# Test_Jig_BMPx2.net
KiCad netlist of a schematic drawn in Altium Designer
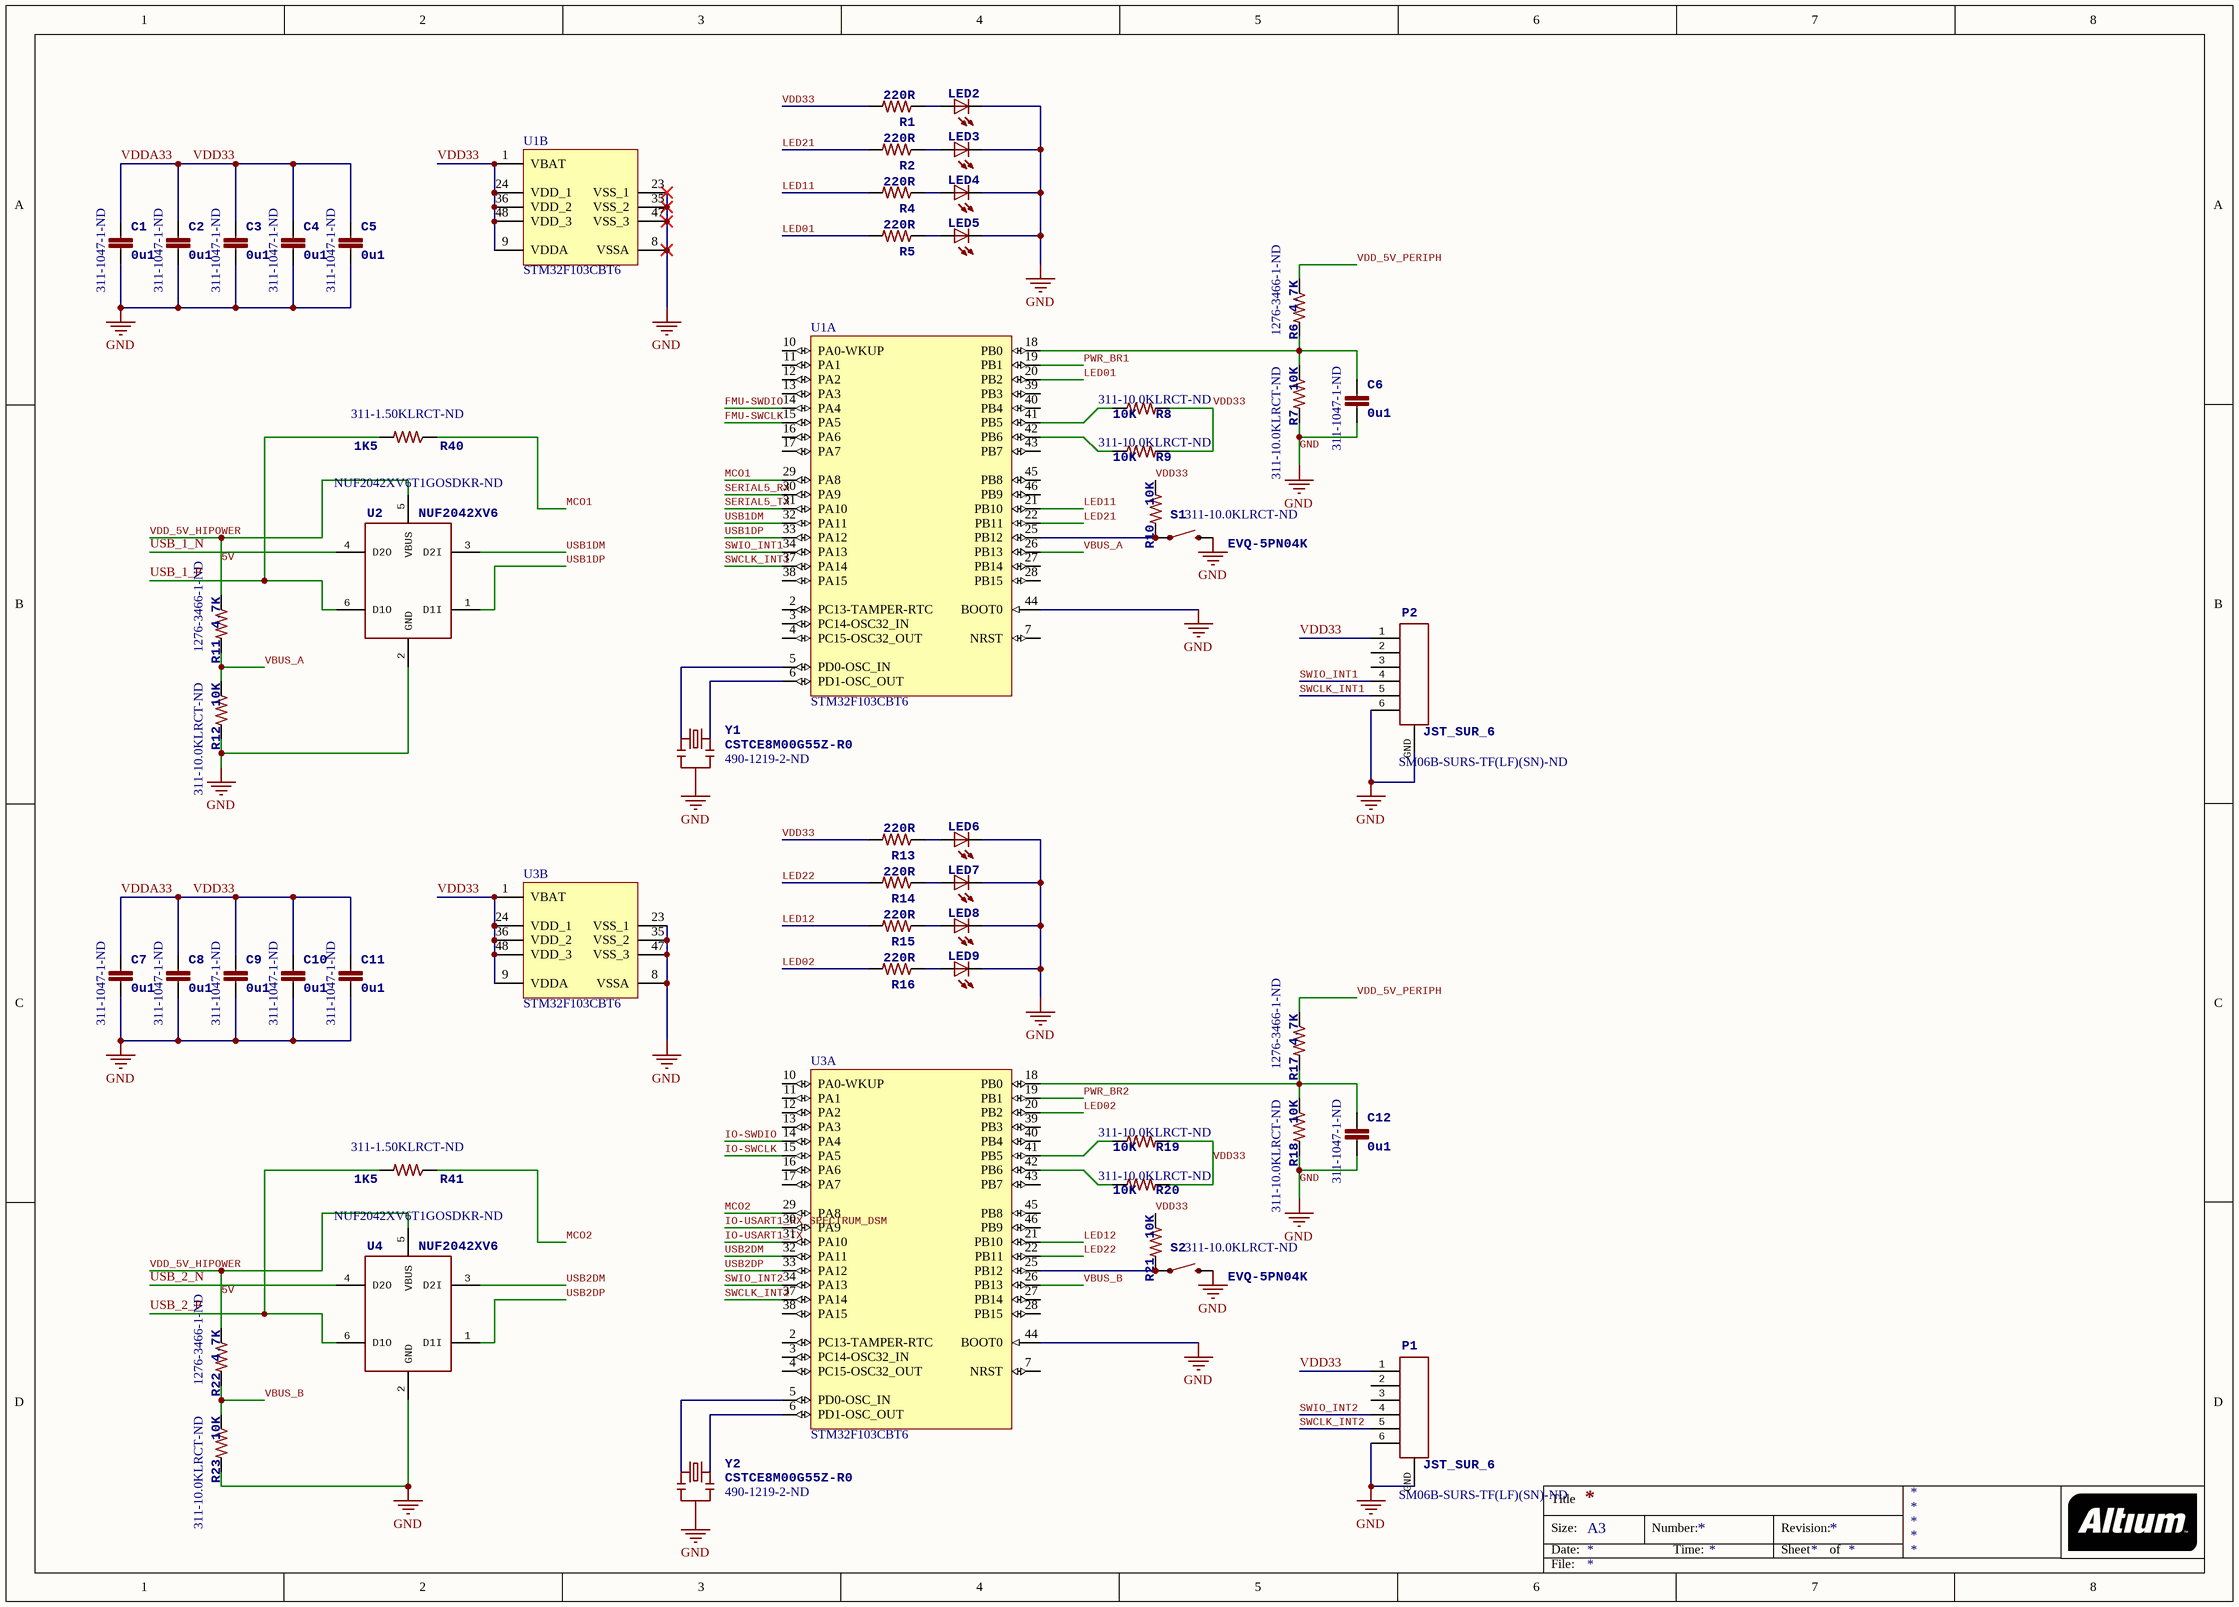
[diagram p0: Test_Jig_BMPx2.SchDoc]

(export (version "E")
  (design (tool "Eeschema 10.0.6"))
  (components
    (comp (ref "C1")
      (value "0u1")
      (footprint "0402-CAP")
      (description "CAP CER 0.1UF 16V Y5V 0402")
      (fields
        (field (name "PARTNO") "CC0402ZRY5V7BB104")
        (field (name "SUPPLIER PART NUMBER 1") "311-1047-1-ND")
        (field (name "3DR_PARTNO") "ECM0700")
      )
      (libsource (lib "pixhawk2") (part "CAP0402"))
    )
    (comp (ref "C2")
      (value "0u1")
      (footprint "0402-CAP")
      (description "CAP CER 0.1UF 16V Y5V 0402")
      (fields
        (field (name "PARTNO") "CC0402ZRY5V7BB104")
        (field (name "SUPPLIER PART NUMBER 1") "311-1047-1-ND")
        (field (name "3DR_PARTNO") "ECM0700")
      )
      (libsource (lib "pixhawk2") (part "CAP0402"))
    )
    (comp (ref "C3")
      (value "0u1")
      (footprint "0402-CAP")
      (description "CAP CER 0.1UF 16V Y5V 0402")
      (fields
        (field (name "PARTNO") "CC0402ZRY5V7BB104")
        (field (name "SUPPLIER PART NUMBER 1") "311-1047-1-ND")
        (field (name "3DR_PARTNO") "ECM0700")
      )
      (libsource (lib "pixhawk2") (part "CAP0402"))
    )
    (comp (ref "C4")
      (value "0u1")
      (footprint "0402-CAP")
      (description "CAP CER 0.1UF 16V Y5V 0402")
      (fields
        (field (name "PARTNO") "CC0402ZRY5V7BB104")
        (field (name "SUPPLIER PART NUMBER 1") "311-1047-1-ND")
        (field (name "3DR_PARTNO") "ECM0700")
      )
      (libsource (lib "pixhawk2") (part "CAP0402"))
    )
    (comp (ref "C5")
      (value "0u1")
      (footprint "0402-CAP")
      (description "CAP CER 0.1UF 16V Y5V 0402")
      (fields
        (field (name "PARTNO") "CC0402ZRY5V7BB104")
        (field (name "SUPPLIER PART NUMBER 1") "311-1047-1-ND")
        (field (name "3DR_PARTNO") "ECM0700")
      )
      (libsource (lib "pixhawk2") (part "CAP0402"))
    )
    (comp (ref "C6")
      (value "0u1")
      (footprint "0402-CAP")
      (description "CAP CER 0.1UF 16V Y5V 0402")
      (fields
        (field (name "PARTNO") "CC0402ZRY5V7BB104")
        (field (name "SUPPLIER PART NUMBER 1") "311-1047-1-ND")
        (field (name "3DR_PARTNO") "ECM0700")
      )
      (libsource (lib "pixhawk2") (part "CAP0402"))
    )
    (comp (ref "C7")
      (value "0u1")
      (footprint "0402-CAP")
      (description "CAP CER 0.1UF 16V Y5V 0402")
      (fields
        (field (name "PARTNO") "CC0402ZRY5V7BB104")
        (field (name "SUPPLIER PART NUMBER 1") "311-1047-1-ND")
        (field (name "3DR_PARTNO") "ECM0700")
      )
      (libsource (lib "pixhawk2") (part "CAP0402"))
    )
    (comp (ref "C8")
      (value "0u1")
      (footprint "0402-CAP")
      (description "CAP CER 0.1UF 16V Y5V 0402")
      (fields
        (field (name "PARTNO") "CC0402ZRY5V7BB104")
        (field (name "SUPPLIER PART NUMBER 1") "311-1047-1-ND")
        (field (name "3DR_PARTNO") "ECM0700")
      )
      (libsource (lib "pixhawk2") (part "CAP0402"))
    )
    (comp (ref "C9")
      (value "0u1")
      (footprint "0402-CAP")
      (description "CAP CER 0.1UF 16V Y5V 0402")
      (fields
        (field (name "PARTNO") "CC0402ZRY5V7BB104")
        (field (name "SUPPLIER PART NUMBER 1") "311-1047-1-ND")
        (field (name "3DR_PARTNO") "ECM0700")
      )
      (libsource (lib "pixhawk2") (part "CAP0402"))
    )
    (comp (ref "C10")
      (value "0u1")
      (footprint "0402-CAP")
      (description "CAP CER 0.1UF 16V Y5V 0402")
      (fields
        (field (name "PARTNO") "CC0402ZRY5V7BB104")
        (field (name "SUPPLIER PART NUMBER 1") "311-1047-1-ND")
        (field (name "3DR_PARTNO") "ECM0700")
      )
      (libsource (lib "pixhawk2") (part "CAP0402"))
    )
    (comp (ref "C11")
      (value "0u1")
      (footprint "0402-CAP")
      (description "CAP CER 0.1UF 16V Y5V 0402")
      (fields
        (field (name "PARTNO") "CC0402ZRY5V7BB104")
        (field (name "SUPPLIER PART NUMBER 1") "311-1047-1-ND")
        (field (name "3DR_PARTNO") "ECM0700")
      )
      (libsource (lib "pixhawk2") (part "CAP0402"))
    )
    (comp (ref "C12")
      (value "0u1")
      (footprint "0402-CAP")
      (description "CAP CER 0.1UF 16V Y5V 0402")
      (fields
        (field (name "PARTNO") "CC0402ZRY5V7BB104")
        (field (name "SUPPLIER PART NUMBER 1") "311-1047-1-ND")
        (field (name "3DR_PARTNO") "ECM0700")
      )
      (libsource (lib "pixhawk2") (part "CAP0402"))
    )
    (comp (ref "LED2")
      (value "LED0603_Green")
      (footprint "0603-LED-Blue")
      (description "LED GREEN ROUND CLEAR SMD")
      (fields (field (name "3DR_PARTNO") "ECM0494") (field (name "PARTNO") "APTD1608CGCK"))
      (libsource (lib "pixhawk2") (part "LED0603_Blue"))
    )
    (comp (ref "LED3")
      (value "LED0603_Green")
      (footprint "0603-LED-Blue")
      (description "LED GREEN ROUND CLEAR SMD")
      (fields (field (name "3DR_PARTNO") "ECM0494") (field (name "PARTNO") "APTD1608CGCK"))
      (libsource (lib "pixhawk2") (part "LED0603_Blue"))
    )
    (comp (ref "LED4")
      (value "LED0603_Green")
      (footprint "0603-LED-Blue")
      (description "LED GREEN ROUND CLEAR SMD")
      (fields (field (name "3DR_PARTNO") "ECM0494") (field (name "PARTNO") "APTD1608CGCK"))
      (libsource (lib "pixhawk2") (part "LED0603_Blue"))
    )
    (comp (ref "LED5")
      (value "LED0603_Green")
      (footprint "0603-LED-Blue")
      (description "LED GREEN ROUND CLEAR SMD")
      (fields (field (name "3DR_PARTNO") "ECM0494") (field (name "PARTNO") "APTD1608CGCK"))
      (libsource (lib "pixhawk2") (part "LED0603_Blue"))
    )
    (comp (ref "LED6")
      (value "LED0603_Green")
      (footprint "0603-LED-Blue")
      (description "LED GREEN ROUND CLEAR SMD")
      (fields (field (name "3DR_PARTNO") "ECM0494") (field (name "PARTNO") "APTD1608CGCK"))
      (libsource (lib "pixhawk2") (part "LED0603_Blue"))
    )
    (comp (ref "LED7")
      (value "LED0603_Green")
      (footprint "0603-LED-Blue")
      (description "LED GREEN ROUND CLEAR SMD")
      (fields (field (name "3DR_PARTNO") "ECM0494") (field (name "PARTNO") "APTD1608CGCK"))
      (libsource (lib "pixhawk2") (part "LED0603_Blue"))
    )
    (comp (ref "LED8")
      (value "LED0603_Green")
      (footprint "0603-LED-Blue")
      (description "LED GREEN ROUND CLEAR SMD")
      (fields (field (name "3DR_PARTNO") "ECM0494") (field (name "PARTNO") "APTD1608CGCK"))
      (libsource (lib "pixhawk2") (part "LED0603_Blue"))
    )
    (comp (ref "LED9")
      (value "LED0603_Green")
      (footprint "0603-LED-Blue")
      (description "LED GREEN ROUND CLEAR SMD")
      (fields (field (name "3DR_PARTNO") "ECM0494") (field (name "PARTNO") "APTD1608CGCK"))
      (libsource (lib "pixhawk2") (part "LED0603_Blue"))
    )
    (comp (ref "P1")
      (value "JST_SUR_6")
      (footprint "JST_SUR_H6")
      (description "Connector, Header, 6Pos, .8mm IDC, R/A, SMD, Tin")
      (fields
        (field (name "SUPPLIER PART NUMBER 1") "SM06B-SURS-TF(LF)(SN)-ND")
        (field (name "3DR_PARTNO") "PRT0442")
      )
      (libsource (lib "PCA_0005_FULL_CB_REV_A") (part "JST_SUR_6"))
    )
    (comp (ref "P2")
      (value "JST_SUR_6")
      (footprint "JST_SUR_H6")
      (description "Connector, Header, 6Pos, .8mm IDC, R/A, SMD, Tin")
      (fields
        (field (name "SUPPLIER PART NUMBER 1") "SM06B-SURS-TF(LF)(SN)-ND")
        (field (name "3DR_PARTNO") "PRT0442")
      )
      (libsource (lib "PCA_0005_FULL_CB_REV_A") (part "JST_SUR_6"))
    )
    (comp (ref "R1")
      (value "220R")
      (footprint "0402-RES")
      (description "RES 220 OHM 1/16W 1% 0402 SMD")
      (fields (field (name "PARTNO") "RC0402FR-07220RL") (field (name "3DR_PARTNO") "ECM0821"))
      (libsource (lib "pixhawk2") (part "RESISTOR0402-RES"))
    )
    (comp (ref "R2")
      (value "220R")
      (footprint "0402-RES")
      (description "RES 220 OHM 1/16W 1% 0402 SMD")
      (fields (field (name "PARTNO") "RC0402FR-07220RL") (field (name "3DR_PARTNO") "ECM0821"))
      (libsource (lib "pixhawk2") (part "RESISTOR0402-RES"))
    )
    (comp (ref "R4")
      (value "220R")
      (footprint "0402-RES")
      (description "RES 220 OHM 1/16W 1% 0402 SMD")
      (fields (field (name "PARTNO") "RC0402FR-07220RL") (field (name "3DR_PARTNO") "ECM0821"))
      (libsource (lib "pixhawk2") (part "RESISTOR0402-RES"))
    )
    (comp (ref "R5")
      (value "220R")
      (footprint "0402-RES")
      (description "RES 220 OHM 1/16W 1% 0402 SMD")
      (fields (field (name "PARTNO") "RC0402FR-07220RL") (field (name "3DR_PARTNO") "ECM0821"))
      (libsource (lib "pixhawk2") (part "RESISTOR0402-RES"))
    )
    (comp (ref "R6")
      (value "4.7K")
      (footprint "0402-RES")
      (description "RES 10K OHM 1/16W 1% 0402 SMD")
      (fields (field (name "PARTNO") "RC1005F472CS") (field (name "SUPPLIER PART NUMBER 1") "1276-3466-1-ND"))
      (libsource (lib "pixhawk2") (part "RESISTOR0402-RES"))
    )
    (comp (ref "R7")
      (value "10K")
      (footprint "0402-RES")
      (description "RES 10K OHM 1/16W 1% 0402 SMD")
      (fields
        (field (name "PARTNO") "RC0402FR-0710KL")
        (field (name "SUPPLIER PART NUMBER 1") "311-10.0KLRCT-ND")
        (field (name "3DR_PARTNO") "ECM0800")
      )
      (libsource (lib "pixhawk2") (part "RESISTOR0402-RES"))
    )
    (comp (ref "R8")
      (value "10K")
      (footprint "0402-RES")
      (description "RES 10K OHM 1/16W 1% 0402 SMD")
      (fields
        (field (name "PARTNO") "RC0402FR-0710KL")
        (field (name "SUPPLIER PART NUMBER 1") "311-10.0KLRCT-ND")
        (field (name "3DR_PARTNO") "ECM0800")
      )
      (libsource (lib "pixhawk2") (part "RESISTOR0402-RES"))
    )
    (comp (ref "R9")
      (value "10K")
      (footprint "0402-RES")
      (description "RES 10K OHM 1/16W 1% 0402 SMD")
      (fields
        (field (name "PARTNO") "RC0402FR-0710KL")
        (field (name "SUPPLIER PART NUMBER 1") "311-10.0KLRCT-ND")
        (field (name "3DR_PARTNO") "ECM0800")
      )
      (libsource (lib "pixhawk2") (part "RESISTOR0402-RES"))
    )
    (comp (ref "R10")
      (value "10K")
      (footprint "0402-RES")
      (description "RES 10K OHM 1/16W 1% 0402 SMD")
      (fields
        (field (name "PARTNO") "RC0402FR-0710KL")
        (field (name "SUPPLIER PART NUMBER 1") "311-10.0KLRCT-ND")
        (field (name "3DR_PARTNO") "ECM0800")
      )
      (libsource (lib "pixhawk2") (part "RESISTOR0402-RES"))
    )
    (comp (ref "R11")
      (value "4.7K")
      (footprint "0402-RES")
      (description "RES 10K OHM 1/16W 1% 0402 SMD")
      (fields (field (name "PARTNO") "RC1005F472CS") (field (name "SUPPLIER PART NUMBER 1") "1276-3466-1-ND"))
      (libsource (lib "pixhawk2") (part "RESISTOR0402-RES"))
    )
    (comp (ref "R12")
      (value "10K")
      (footprint "0402-RES")
      (description "RES 10K OHM 1/16W 1% 0402 SMD")
      (fields
        (field (name "PARTNO") "RC0402FR-0710KL")
        (field (name "SUPPLIER PART NUMBER 1") "311-10.0KLRCT-ND")
        (field (name "3DR_PARTNO") "ECM0800")
      )
      (libsource (lib "pixhawk2") (part "RESISTOR0402-RES"))
    )
    (comp (ref "R13")
      (value "220R")
      (footprint "0402-RES")
      (description "RES 220 OHM 1/16W 1% 0402 SMD")
      (fields (field (name "PARTNO") "RC0402FR-07220RL") (field (name "3DR_PARTNO") "ECM0821"))
      (libsource (lib "pixhawk2") (part "RESISTOR0402-RES"))
    )
    (comp (ref "R14")
      (value "220R")
      (footprint "0402-RES")
      (description "RES 220 OHM 1/16W 1% 0402 SMD")
      (fields (field (name "PARTNO") "RC0402FR-07220RL") (field (name "3DR_PARTNO") "ECM0821"))
      (libsource (lib "pixhawk2") (part "RESISTOR0402-RES"))
    )
    (comp (ref "R15")
      (value "220R")
      (footprint "0402-RES")
      (description "RES 220 OHM 1/16W 1% 0402 SMD")
      (fields (field (name "PARTNO") "RC0402FR-07220RL") (field (name "3DR_PARTNO") "ECM0821"))
      (libsource (lib "pixhawk2") (part "RESISTOR0402-RES"))
    )
    (comp (ref "R16")
      (value "220R")
      (footprint "0402-RES")
      (description "RES 220 OHM 1/16W 1% 0402 SMD")
      (fields (field (name "PARTNO") "RC0402FR-07220RL") (field (name "3DR_PARTNO") "ECM0821"))
      (libsource (lib "pixhawk2") (part "RESISTOR0402-RES"))
    )
    (comp (ref "R17")
      (value "4.7K")
      (footprint "0402-RES")
      (description "RES 10K OHM 1/16W 1% 0402 SMD")
      (fields (field (name "PARTNO") "RC1005F472CS") (field (name "SUPPLIER PART NUMBER 1") "1276-3466-1-ND"))
      (libsource (lib "pixhawk2") (part "RESISTOR0402-RES"))
    )
    (comp (ref "R18")
      (value "10K")
      (footprint "0402-RES")
      (description "RES 10K OHM 1/16W 1% 0402 SMD")
      (fields
        (field (name "PARTNO") "RC0402FR-0710KL")
        (field (name "SUPPLIER PART NUMBER 1") "311-10.0KLRCT-ND")
        (field (name "3DR_PARTNO") "ECM0800")
      )
      (libsource (lib "pixhawk2") (part "RESISTOR0402-RES"))
    )
    (comp (ref "R19")
      (value "10K")
      (footprint "0402-RES")
      (description "RES 10K OHM 1/16W 1% 0402 SMD")
      (fields
        (field (name "PARTNO") "RC0402FR-0710KL")
        (field (name "SUPPLIER PART NUMBER 1") "311-10.0KLRCT-ND")
        (field (name "3DR_PARTNO") "ECM0800")
      )
      (libsource (lib "pixhawk2") (part "RESISTOR0402-RES"))
    )
    (comp (ref "R20")
      (value "10K")
      (footprint "0402-RES")
      (description "RES 10K OHM 1/16W 1% 0402 SMD")
      (fields
        (field (name "PARTNO") "RC0402FR-0710KL")
        (field (name "SUPPLIER PART NUMBER 1") "311-10.0KLRCT-ND")
        (field (name "3DR_PARTNO") "ECM0800")
      )
      (libsource (lib "pixhawk2") (part "RESISTOR0402-RES"))
    )
    (comp (ref "R21")
      (value "10K")
      (footprint "0402-RES")
      (description "RES 10K OHM 1/16W 1% 0402 SMD")
      (fields
        (field (name "PARTNO") "RC0402FR-0710KL")
        (field (name "SUPPLIER PART NUMBER 1") "311-10.0KLRCT-ND")
        (field (name "3DR_PARTNO") "ECM0800")
      )
      (libsource (lib "pixhawk2") (part "RESISTOR0402-RES"))
    )
    (comp (ref "R22")
      (value "4.7K")
      (footprint "0402-RES")
      (description "RES 10K OHM 1/16W 1% 0402 SMD")
      (fields (field (name "PARTNO") "RC1005F472CS") (field (name "SUPPLIER PART NUMBER 1") "1276-3466-1-ND"))
      (libsource (lib "pixhawk2") (part "RESISTOR0402-RES"))
    )
    (comp (ref "R23")
      (value "10K")
      (footprint "0402-RES")
      (description "RES 10K OHM 1/16W 1% 0402 SMD")
      (fields
        (field (name "PARTNO") "RC0402FR-0710KL")
        (field (name "SUPPLIER PART NUMBER 1") "311-10.0KLRCT-ND")
        (field (name "3DR_PARTNO") "ECM0800")
      )
      (libsource (lib "pixhawk2") (part "RESISTOR0402-RES"))
    )
    (comp (ref "R40")
      (value "1K5")
      (footprint "0402-RES")
      (description "RES 1.5K OHM 1/16W 1% 0402 SMD")
      (fields
        (field (name "PARTNO") "RC0402FR-071K5L")
        (field (name "SUPPLIER PART NUMBER 1") "311-1.50KLRCT-ND")
        (field (name "3DR_PARTNO") "ECM0803")
      )
      (libsource (lib "pixhawk2") (part "RESISTOR0402-RES"))
    )
    (comp (ref "R41")
      (value "1K5")
      (footprint "0402-RES")
      (description "RES 1.5K OHM 1/16W 1% 0402 SMD")
      (fields
        (field (name "PARTNO") "RC0402FR-071K5L")
        (field (name "SUPPLIER PART NUMBER 1") "311-1.50KLRCT-ND")
        (field (name "3DR_PARTNO") "ECM0803")
      )
      (libsource (lib "pixhawk2") (part "RESISTOR0402-RES"))
    )
    (comp (ref "S1")
      (value "EVQ-5PN04K")
      (footprint "TACTILE-SWITCH-1101NE")
      (libsource (lib "pixhawk2") (part "SWITCH-MOMENTARY-2-SMD-1101NE"))
    )
    (comp (ref "S2")
      (value "EVQ-5PN04K")
      (footprint "TACTILE-SWITCH-1101NE")
      (libsource (lib "pixhawk2") (part "SWITCH-MOMENTARY-2-SMD-1101NE"))
    )
    (comp (ref "U1")
      (value "STM32F103CBT6")
      (footprint "STM-LQFP48_N")
      (libsource (lib "STMicroelectronics STM32 F1") (part "STM32F103CBT6"))
    )
    (comp (ref "U2")
      (value "NUF2042XV6")
      (footprint "SOT563-6")
      (description "IC FILTER USB ESD PROTECT SOT363")
      (fields
        (field (name "PARTNO") "NUF2042XV6T1G")
        (field (name "SUPPLIER PART NUMBER 1") "NUF2042XV6T1GOSDKR-ND")
        (field (name "3DR_PARTNO") "ECM0836")
      )
      (libsource (lib "pixhawk2") (part "NUF2042XV6"))
    )
    (comp (ref "U3")
      (value "STM32F103CBT6")
      (footprint "STM-LQFP48_N")
      (libsource (lib "STMicroelectronics STM32 F1") (part "STM32F103CBT6"))
    )
    (comp (ref "U4")
      (value "NUF2042XV6")
      (footprint "SOT563-6")
      (description "IC FILTER USB ESD PROTECT SOT363")
      (fields
        (field (name "PARTNO") "NUF2042XV6T1G")
        (field (name "SUPPLIER PART NUMBER 1") "NUF2042XV6T1GOSDKR-ND")
        (field (name "3DR_PARTNO") "ECM0836")
      )
      (libsource (lib "pixhawk2") (part "NUF2042XV6"))
    )
    (comp (ref "Y1")
      (value "CSTCE8M00G55Z-R0")
      (footprint "RESONATOR-SMD")
      (fields (field (name "SUPPLIER PART NUMBER 1") "490-1219-2-ND"))
      (libsource (lib "SparkFun") (part "RESONATORSMD"))
    )
    (comp (ref "Y2")
      (value "CSTCE8M00G55Z-R0")
      (footprint "RESONATOR-SMD")
      (fields (field (name "SUPPLIER PART NUMBER 1") "490-1219-2-ND"))
      (libsource (lib "SparkFun") (part "RESONATORSMD"))
    )
  )
  (nets
    (net (code "1") (name "/5V") (class "Default")
      (node (ref "R11") (pin "P$1") (pinfunction "1_P$1") (pintype "passive"))
      (node (ref "R22") (pin "P$1") (pinfunction "1_P$1") (pintype "passive"))
      (node (ref "U2") (pin "5") (pinfunction "VBUS_5") (pintype "passive"))
      (node (ref "U4") (pin "5") (pinfunction "VBUS_5") (pintype "passive"))
    )
    (net (code "2") (name "/FMU-SWCLK") (class "Default")
      (node (ref "U1") (pin "15") (pinfunction "PA5_15") (pintype "bidirectional"))
    )
    (net (code "3") (name "/FMU-SWDIO") (class "Default")
      (node (ref "U1") (pin "14") (pinfunction "PA4_14") (pintype "bidirectional"))
    )
    (net (code "4") (name "/IO-SWCLK") (class "Default")
      (node (ref "U3") (pin "15") (pinfunction "PA5_15") (pintype "bidirectional"))
    )
    (net (code "5") (name "/IO-SWDIO") (class "Default")
      (node (ref "U3") (pin "14") (pinfunction "PA4_14") (pintype "bidirectional"))
    )
    (net (code "6") (name "/IO-USART1_RX_SPECTRUM_DSM") (class "Default")
      (node (ref "U3") (pin "30") (pinfunction "PA9_30") (pintype "bidirectional"))
    )
    (net (code "7") (name "/IO-USART1_TX") (class "Default")
      (node (ref "U3") (pin "31") (pinfunction "PA10_31") (pintype "bidirectional"))
    )
    (net (code "8") (name "/LED01") (class "Default")
      (node (ref "R5") (pin "P$2") (pinfunction "2_P$2") (pintype "passive"))
      (node (ref "U1") (pin "20") (pinfunction "PB2_20") (pintype "bidirectional"))
    )
    (net (code "9") (name "/LED02") (class "Default")
      (node (ref "R16") (pin "P$2") (pinfunction "2_P$2") (pintype "passive"))
      (node (ref "U3") (pin "20") (pinfunction "PB2_20") (pintype "bidirectional"))
    )
    (net (code "10") (name "/LED11") (class "Default")
      (node (ref "R4") (pin "P$2") (pinfunction "2_P$2") (pintype "passive"))
      (node (ref "U1") (pin "21") (pinfunction "PB10_21") (pintype "bidirectional"))
    )
    (net (code "11") (name "/LED12") (class "Default")
      (node (ref "R15") (pin "P$2") (pinfunction "2_P$2") (pintype "passive"))
      (node (ref "U3") (pin "21") (pinfunction "PB10_21") (pintype "bidirectional"))
    )
    (net (code "12") (name "/LED21") (class "Default")
      (node (ref "R2") (pin "P$2") (pinfunction "2_P$2") (pintype "passive"))
      (node (ref "U1") (pin "22") (pinfunction "PB11_22") (pintype "bidirectional"))
    )
    (net (code "13") (name "/LED22") (class "Default")
      (node (ref "R14") (pin "P$2") (pinfunction "2_P$2") (pintype "passive"))
      (node (ref "U3") (pin "22") (pinfunction "PB11_22") (pintype "bidirectional"))
    )
    (net (code "14") (name "/MCO1") (class "Default")
      (node (ref "R40") (pin "P$1") (pinfunction "1_P$1") (pintype "passive"))
      (node (ref "U1") (pin "29") (pinfunction "PA8_29") (pintype "bidirectional"))
    )
    (net (code "15") (name "/MCO2") (class "Default")
      (node (ref "R41") (pin "P$1") (pinfunction "1_P$1") (pintype "passive"))
      (node (ref "U3") (pin "29") (pinfunction "PA8_29") (pintype "bidirectional"))
    )
    (net (code "16") (name "/PWR_BR1") (class "Default")
      (node (ref "U1") (pin "19") (pinfunction "PB1_19") (pintype "bidirectional"))
    )
    (net (code "17") (name "/PWR_BR2") (class "Default")
      (node (ref "U3") (pin "19") (pinfunction "PB1_19") (pintype "bidirectional"))
    )
    (net (code "18") (name "/SERIAL5_RX") (class "Default")
      (node (ref "U1") (pin "30") (pinfunction "PA9_30") (pintype "bidirectional"))
    )
    (net (code "19") (name "/SERIAL5_TX") (class "Default")
      (node (ref "U1") (pin "31") (pinfunction "PA10_31") (pintype "bidirectional"))
    )
    (net (code "20") (name "/SWCLK_INT1") (class "Default")
      (node (ref "P2") (pin "5") (pinfunction "5_5") (pintype "passive"))
      (node (ref "U1") (pin "37") (pinfunction "PA14_37") (pintype "bidirectional"))
    )
    (net (code "21") (name "/SWCLK_INT2") (class "Default")
      (node (ref "P1") (pin "5") (pinfunction "5_5") (pintype "passive"))
      (node (ref "U3") (pin "37") (pinfunction "PA14_37") (pintype "bidirectional"))
    )
    (net (code "22") (name "/SWIO_INT1") (class "Default")
      (node (ref "P2") (pin "4") (pinfunction "4_4") (pintype "passive"))
      (node (ref "U1") (pin "34") (pinfunction "PA13_34") (pintype "bidirectional"))
    )
    (net (code "23") (name "/SWIO_INT2") (class "Default")
      (node (ref "P1") (pin "4") (pinfunction "4_4") (pintype "passive"))
      (node (ref "U3") (pin "34") (pinfunction "PA13_34") (pintype "bidirectional"))
    )
    (net (code "24") (name "/USB1DM") (class "Default")
      (node (ref "U1") (pin "32") (pinfunction "PA11_32") (pintype "bidirectional"))
      (node (ref "U2") (pin "3") (pinfunction "D2I_3") (pintype "passive"))
    )
    (net (code "25") (name "/USB1DP") (class "Default")
      (node (ref "U1") (pin "33") (pinfunction "PA12_33") (pintype "bidirectional"))
      (node (ref "U2") (pin "1") (pinfunction "D1I_1") (pintype "passive"))
    )
    (net (code "26") (name "/USB2DM") (class "Default")
      (node (ref "U3") (pin "32") (pinfunction "PA11_32") (pintype "bidirectional"))
      (node (ref "U4") (pin "3") (pinfunction "D2I_3") (pintype "passive"))
    )
    (net (code "27") (name "/USB2DP") (class "Default")
      (node (ref "U3") (pin "33") (pinfunction "PA12_33") (pintype "bidirectional"))
      (node (ref "U4") (pin "1") (pinfunction "D1I_1") (pintype "passive"))
    )
    (net (code "28") (name "/USB_1_N") (class "Default")
      (node (ref "U2") (pin "4") (pinfunction "D2O_4") (pintype "passive"))
    )
    (net (code "29") (name "/USB_1_P") (class "Default")
      (node (ref "R40") (pin "P$2") (pinfunction "2_P$2") (pintype "passive"))
      (node (ref "U2") (pin "6") (pinfunction "D1O_6") (pintype "passive"))
    )
    (net (code "30") (name "/USB_2_N") (class "Default")
      (node (ref "U4") (pin "4") (pinfunction "D2O_4") (pintype "passive"))
    )
    (net (code "31") (name "/USB_2_P") (class "Default")
      (node (ref "R41") (pin "P$2") (pinfunction "2_P$2") (pintype "passive"))
      (node (ref "U4") (pin "6") (pinfunction "D1O_6") (pintype "passive"))
    )
    (net (code "32") (name "/VBUS_A") (class "Default")
      (node (ref "R11") (pin "P$2") (pinfunction "2_P$2") (pintype "passive"))
      (node (ref "R12") (pin "P$1") (pinfunction "1_P$1") (pintype "passive"))
      (node (ref "U1") (pin "26") (pinfunction "PB13_26") (pintype "bidirectional"))
    )
    (net (code "33") (name "/VBUS_B") (class "Default")
      (node (ref "R22") (pin "P$2") (pinfunction "2_P$2") (pintype "passive"))
      (node (ref "R23") (pin "P$1") (pinfunction "1_P$1") (pintype "passive"))
      (node (ref "U3") (pin "26") (pinfunction "PB13_26") (pintype "bidirectional"))
    )
    (net (code "34") (name "/VDD33") (class "Default")
      (node (ref "C1") (pin "P$1") (pinfunction "1_P$1") (pintype "passive"))
      (node (ref "C10") (pin "P$1") (pinfunction "1_P$1") (pintype "passive"))
      (node (ref "C11") (pin "P$1") (pinfunction "1_P$1") (pintype "passive"))
      (node (ref "C2") (pin "P$1") (pinfunction "1_P$1") (pintype "passive"))
      (node (ref "C3") (pin "P$1") (pinfunction "1_P$1") (pintype "passive"))
      (node (ref "C4") (pin "P$1") (pinfunction "1_P$1") (pintype "passive"))
      (node (ref "C5") (pin "P$1") (pinfunction "1_P$1") (pintype "passive"))
      (node (ref "C7") (pin "P$1") (pinfunction "1_P$1") (pintype "passive"))
      (node (ref "C8") (pin "P$1") (pinfunction "1_P$1") (pintype "passive"))
      (node (ref "C9") (pin "P$1") (pinfunction "1_P$1") (pintype "passive"))
      (node (ref "P1") (pin "1") (pinfunction "1_1") (pintype "passive"))
      (node (ref "P2") (pin "1") (pinfunction "1_1") (pintype "passive"))
      (node (ref "R1") (pin "P$2") (pinfunction "2_P$2") (pintype "passive"))
      (node (ref "R10") (pin "P$1") (pinfunction "1_P$1") (pintype "passive"))
      (node (ref "R13") (pin "P$2") (pinfunction "2_P$2") (pintype "passive"))
      (node (ref "R19") (pin "P$2") (pinfunction "2_P$2") (pintype "passive"))
      (node (ref "R20") (pin "P$2") (pinfunction "2_P$2") (pintype "passive"))
      (node (ref "R21") (pin "P$1") (pinfunction "1_P$1") (pintype "passive"))
      (node (ref "R8") (pin "P$2") (pinfunction "2_P$2") (pintype "passive"))
      (node (ref "R9") (pin "P$2") (pinfunction "2_P$2") (pintype "passive"))
      (node (ref "U1") (pin "1") (pinfunction "VBAT_1") (pintype "power_in"))
      (node (ref "U1") (pin "24") (pinfunction "VDD_1_24") (pintype "power_in"))
      (node (ref "U1") (pin "36") (pinfunction "VDD_2_36") (pintype "power_in"))
      (node (ref "U1") (pin "48") (pinfunction "VDD_3_48") (pintype "power_in"))
      (node (ref "U1") (pin "9") (pinfunction "VDDA_9") (pintype "power_in"))
      (node (ref "U3") (pin "1") (pinfunction "VBAT_1") (pintype "power_in"))
      (node (ref "U3") (pin "24") (pinfunction "VDD_1_24") (pintype "power_in"))
      (node (ref "U3") (pin "36") (pinfunction "VDD_2_36") (pintype "power_in"))
      (node (ref "U3") (pin "48") (pinfunction "VDD_3_48") (pintype "power_in"))
      (node (ref "U3") (pin "9") (pinfunction "VDDA_9") (pintype "power_in"))
    )
    (net (code "35") (name "/VDD_5V_PERIPH") (class "Default")
      (node (ref "R17") (pin "P$1") (pinfunction "1_P$1") (pintype "passive"))
      (node (ref "R6") (pin "P$1") (pinfunction "1_P$1") (pintype "passive"))
    )
    (net (code "36") (name "GND") (class "Default")
      (node (ref "C1") (pin "P$2") (pinfunction "2_P$2") (pintype "passive"))
      (node (ref "C10") (pin "P$2") (pinfunction "2_P$2") (pintype "passive"))
      (node (ref "C11") (pin "P$2") (pinfunction "2_P$2") (pintype "passive"))
      (node (ref "C12") (pin "P$2") (pinfunction "2_P$2") (pintype "passive"))
      (node (ref "C2") (pin "P$2") (pinfunction "2_P$2") (pintype "passive"))
      (node (ref "C3") (pin "P$2") (pinfunction "2_P$2") (pintype "passive"))
      (node (ref "C4") (pin "P$2") (pinfunction "2_P$2") (pintype "passive"))
      (node (ref "C5") (pin "P$2") (pinfunction "2_P$2") (pintype "passive"))
      (node (ref "C6") (pin "P$2") (pinfunction "2_P$2") (pintype "passive"))
      (node (ref "C7") (pin "P$2") (pinfunction "2_P$2") (pintype "passive"))
      (node (ref "C8") (pin "P$2") (pinfunction "2_P$2") (pintype "passive"))
      (node (ref "C9") (pin "P$2") (pinfunction "2_P$2") (pintype "passive"))
      (node (ref "LED2") (pin "C") (pinfunction "C_C") (pintype "passive"))
      (node (ref "LED3") (pin "C") (pinfunction "C_C") (pintype "passive"))
      (node (ref "LED4") (pin "C") (pinfunction "C_C") (pintype "passive"))
      (node (ref "LED5") (pin "C") (pinfunction "C_C") (pintype "passive"))
      (node (ref "LED6") (pin "C") (pinfunction "C_C") (pintype "passive"))
      (node (ref "LED7") (pin "C") (pinfunction "C_C") (pintype "passive"))
      (node (ref "LED8") (pin "C") (pinfunction "C_C") (pintype "passive"))
      (node (ref "LED9") (pin "C") (pinfunction "C_C") (pintype "passive"))
      (node (ref "P1") (pin "6") (pinfunction "6_6") (pintype "passive"))
      (node (ref "P1") (pin "GND") (pinfunction "GND_GND") (pintype "passive"))
      (node (ref "P2") (pin "6") (pinfunction "6_6") (pintype "passive"))
      (node (ref "P2") (pin "GND") (pinfunction "GND_GND") (pintype "passive"))
      (node (ref "R12") (pin "P$2") (pinfunction "2_P$2") (pintype "passive"))
      (node (ref "R18") (pin "P$2") (pinfunction "2_P$2") (pintype "passive"))
      (node (ref "R23") (pin "P$2") (pinfunction "2_P$2") (pintype "passive"))
      (node (ref "R7") (pin "P$2") (pinfunction "2_P$2") (pintype "passive"))
      (node (ref "S1") (pin "2") (pinfunction "2_2") (pintype "passive"))
      (node (ref "S2") (pin "2") (pinfunction "2_2") (pintype "passive"))
      (node (ref "U1") (pin "23") (pinfunction "VSS_1_23") (pintype "power_in"))
      (node (ref "U1") (pin "35") (pinfunction "VSS_2_35") (pintype "power_in"))
      (node (ref "U1") (pin "44") (pinfunction "BOOT0_44") (pintype "input"))
      (node (ref "U1") (pin "47") (pinfunction "VSS_3_47") (pintype "power_in"))
      (node (ref "U1") (pin "8") (pinfunction "VSSA_8") (pintype "power_in"))
      (node (ref "U2") (pin "2") (pinfunction "GND_2") (pintype "passive"))
      (node (ref "U3") (pin "23") (pinfunction "VSS_1_23") (pintype "power_in"))
      (node (ref "U3") (pin "35") (pinfunction "VSS_2_35") (pintype "power_in"))
      (node (ref "U3") (pin "44") (pinfunction "BOOT0_44") (pintype "input"))
      (node (ref "U3") (pin "47") (pinfunction "VSS_3_47") (pintype "power_in"))
      (node (ref "U3") (pin "8") (pinfunction "VSSA_8") (pintype "power_in"))
      (node (ref "U4") (pin "2") (pinfunction "GND_2") (pintype "passive"))
      (node (ref "Y1") (pin "2") (pinfunction "2_2") (pintype "passive"))
      (node (ref "Y2") (pin "2") (pinfunction "2_2") (pintype "passive"))
    )
    (net (code "37") (name "Net-(C6-1)") (class "Default")
      (node (ref "C6") (pin "P$1") (pinfunction "1_P$1") (pintype "passive"))
      (node (ref "R6") (pin "P$2") (pinfunction "2_P$2") (pintype "passive"))
      (node (ref "R7") (pin "P$1") (pinfunction "1_P$1") (pintype "passive"))
      (node (ref "U1") (pin "18") (pinfunction "PB0_18") (pintype "bidirectional"))
    )
    (net (code "38") (name "Net-(C12-1)") (class "Default")
      (node (ref "C12") (pin "P$1") (pinfunction "1_P$1") (pintype "passive"))
      (node (ref "R17") (pin "P$2") (pinfunction "2_P$2") (pintype "passive"))
      (node (ref "R18") (pin "P$1") (pinfunction "1_P$1") (pintype "passive"))
      (node (ref "U3") (pin "18") (pinfunction "PB0_18") (pintype "bidirectional"))
    )
    (net (code "39") (name "Net-(R1-1)") (class "Default")
      (node (ref "LED2") (pin "A") (pinfunction "A_A") (pintype "passive"))
      (node (ref "R1") (pin "P$1") (pinfunction "1_P$1") (pintype "passive"))
    )
    (net (code "40") (name "Net-(R2-1)") (class "Default")
      (node (ref "LED3") (pin "A") (pinfunction "A_A") (pintype "passive"))
      (node (ref "R2") (pin "P$1") (pinfunction "1_P$1") (pintype "passive"))
    )
    (net (code "41") (name "Net-(R4-1)") (class "Default")
      (node (ref "LED4") (pin "A") (pinfunction "A_A") (pintype "passive"))
      (node (ref "R4") (pin "P$1") (pinfunction "1_P$1") (pintype "passive"))
    )
    (net (code "42") (name "Net-(R5-1)") (class "Default")
      (node (ref "LED5") (pin "A") (pinfunction "A_A") (pintype "passive"))
      (node (ref "R5") (pin "P$1") (pinfunction "1_P$1") (pintype "passive"))
    )
    (net (code "43") (name "Net-(R8-1)") (class "Default")
      (node (ref "R8") (pin "P$1") (pinfunction "1_P$1") (pintype "passive"))
      (node (ref "U1") (pin "41") (pinfunction "PB5_41") (pintype "bidirectional"))
    )
    (net (code "44") (name "Net-(R9-1)") (class "Default")
      (node (ref "R9") (pin "P$1") (pinfunction "1_P$1") (pintype "passive"))
      (node (ref "U1") (pin "42") (pinfunction "PB6_42") (pintype "bidirectional"))
    )
    (net (code "45") (name "Net-(R10-2)") (class "Default")
      (node (ref "R10") (pin "P$2") (pinfunction "2_P$2") (pintype "passive"))
      (node (ref "S1") (pin "1") (pinfunction "1_1") (pintype "passive"))
      (node (ref "U1") (pin "25") (pinfunction "PB12_25") (pintype "bidirectional"))
    )
    (net (code "46") (name "Net-(R13-1)") (class "Default")
      (node (ref "LED6") (pin "A") (pinfunction "A_A") (pintype "passive"))
      (node (ref "R13") (pin "P$1") (pinfunction "1_P$1") (pintype "passive"))
    )
    (net (code "47") (name "Net-(R14-1)") (class "Default")
      (node (ref "LED7") (pin "A") (pinfunction "A_A") (pintype "passive"))
      (node (ref "R14") (pin "P$1") (pinfunction "1_P$1") (pintype "passive"))
    )
    (net (code "48") (name "Net-(R15-1)") (class "Default")
      (node (ref "LED8") (pin "A") (pinfunction "A_A") (pintype "passive"))
      (node (ref "R15") (pin "P$1") (pinfunction "1_P$1") (pintype "passive"))
    )
    (net (code "49") (name "Net-(R16-1)") (class "Default")
      (node (ref "LED9") (pin "A") (pinfunction "A_A") (pintype "passive"))
      (node (ref "R16") (pin "P$1") (pinfunction "1_P$1") (pintype "passive"))
    )
    (net (code "50") (name "Net-(R19-1)") (class "Default")
      (node (ref "R19") (pin "P$1") (pinfunction "1_P$1") (pintype "passive"))
      (node (ref "U3") (pin "41") (pinfunction "PB5_41") (pintype "bidirectional"))
    )
    (net (code "51") (name "Net-(R20-1)") (class "Default")
      (node (ref "R20") (pin "P$1") (pinfunction "1_P$1") (pintype "passive"))
      (node (ref "U3") (pin "42") (pinfunction "PB6_42") (pintype "bidirectional"))
    )
    (net (code "52") (name "Net-(R21-2)") (class "Default")
      (node (ref "R21") (pin "P$2") (pinfunction "2_P$2") (pintype "passive"))
      (node (ref "S2") (pin "1") (pinfunction "1_1") (pintype "passive"))
      (node (ref "U3") (pin "25") (pinfunction "PB12_25") (pintype "bidirectional"))
    )
    (net (code "53") (name "Net-(U1A-PD0-OSC_IN)") (class "Default")
      (node (ref "U1") (pin "5") (pinfunction "PD0-OSC_IN_5") (pintype "bidirectional"))
      (node (ref "Y1") (pin "1") (pinfunction "1_1") (pintype "passive"))
    )
    (net (code "54") (name "Net-(U1A-PD1-OSC_OUT)") (class "Default")
      (node (ref "U1") (pin "6") (pinfunction "PD1-OSC_OUT_6") (pintype "bidirectional"))
      (node (ref "Y1") (pin "3") (pinfunction "3_3") (pintype "passive"))
    )
    (net (code "55") (name "Net-(U3A-PD0-OSC_IN)") (class "Default")
      (node (ref "U3") (pin "5") (pinfunction "PD0-OSC_IN_5") (pintype "bidirectional"))
      (node (ref "Y2") (pin "1") (pinfunction "1_1") (pintype "passive"))
    )
    (net (code "56") (name "Net-(U3A-PD1-OSC_OUT)") (class "Default")
      (node (ref "U3") (pin "6") (pinfunction "PD1-OSC_OUT_6") (pintype "bidirectional"))
      (node (ref "Y2") (pin "3") (pinfunction "3_3") (pintype "passive"))
    )
    (net (code "57") (name "unconnected-(P1-Pad2)") (class "Default")
      (node (ref "P1") (pin "2") (pinfunction "2_2") (pintype "passive"))
    )
    (net (code "58") (name "unconnected-(P1-Pad3)") (class "Default")
      (node (ref "P1") (pin "3") (pinfunction "3_3") (pintype "passive"))
    )
    (net (code "59") (name "unconnected-(P2-Pad2)") (class "Default")
      (node (ref "P2") (pin "2") (pinfunction "2_2") (pintype "passive"))
    )
    (net (code "60") (name "unconnected-(P2-Pad3)") (class "Default")
      (node (ref "P2") (pin "3") (pinfunction "3_3") (pintype "passive"))
    )
    (net (code "61") (name "unconnected-(U1A-NRST-Pad7)") (class "Default")
      (node (ref "U1") (pin "7") (pinfunction "NRST_7") (pintype "bidirectional"))
    )
    (net (code "62") (name "unconnected-(U1A-PA0-WKUP-Pad10)") (class "Default")
      (node (ref "U1") (pin "10") (pinfunction "PA0-WKUP_10") (pintype "bidirectional"))
    )
    (net (code "63") (name "unconnected-(U1A-PA1-Pad11)") (class "Default")
      (node (ref "U1") (pin "11") (pinfunction "PA1_11") (pintype "bidirectional"))
    )
    (net (code "64") (name "unconnected-(U1A-PA2-Pad12)") (class "Default")
      (node (ref "U1") (pin "12") (pinfunction "PA2_12") (pintype "bidirectional"))
    )
    (net (code "65") (name "unconnected-(U1A-PA3-Pad13)") (class "Default")
      (node (ref "U1") (pin "13") (pinfunction "PA3_13") (pintype "bidirectional"))
    )
    (net (code "66") (name "unconnected-(U1A-PA6-Pad16)") (class "Default")
      (node (ref "U1") (pin "16") (pinfunction "PA6_16") (pintype "bidirectional"))
    )
    (net (code "67") (name "unconnected-(U1A-PA7-Pad17)") (class "Default")
      (node (ref "U1") (pin "17") (pinfunction "PA7_17") (pintype "bidirectional"))
    )
    (net (code "68") (name "unconnected-(U1A-PA15-Pad38)") (class "Default")
      (node (ref "U1") (pin "38") (pinfunction "PA15_38") (pintype "bidirectional"))
    )
    (net (code "69") (name "unconnected-(U1A-PB3-Pad39)") (class "Default")
      (node (ref "U1") (pin "39") (pinfunction "PB3_39") (pintype "bidirectional"))
    )
    (net (code "70") (name "unconnected-(U1A-PB4-Pad40)") (class "Default")
      (node (ref "U1") (pin "40") (pinfunction "PB4_40") (pintype "bidirectional"))
    )
    (net (code "71") (name "unconnected-(U1A-PB7-Pad43)") (class "Default")
      (node (ref "U1") (pin "43") (pinfunction "PB7_43") (pintype "bidirectional"))
    )
    (net (code "72") (name "unconnected-(U1A-PB8-Pad45)") (class "Default")
      (node (ref "U1") (pin "45") (pinfunction "PB8_45") (pintype "bidirectional"))
    )
    (net (code "73") (name "unconnected-(U1A-PB9-Pad46)") (class "Default")
      (node (ref "U1") (pin "46") (pinfunction "PB9_46") (pintype "bidirectional"))
    )
    (net (code "74") (name "unconnected-(U1A-PB14-Pad27)") (class "Default")
      (node (ref "U1") (pin "27") (pinfunction "PB14_27") (pintype "bidirectional"))
    )
    (net (code "75") (name "unconnected-(U1A-PB15-Pad28)") (class "Default")
      (node (ref "U1") (pin "28") (pinfunction "PB15_28") (pintype "bidirectional"))
    )
    (net (code "76") (name "unconnected-(U1A-PC13-TAMPER-RTC-Pad2)") (class "Default")
      (node (ref "U1") (pin "2") (pinfunction "PC13-TAMPER-RTC_2") (pintype "bidirectional"))
    )
    (net (code "77") (name "unconnected-(U1A-PC14-OSC32_IN-Pad3)") (class "Default")
      (node (ref "U1") (pin "3") (pinfunction "PC14-OSC32_IN_3") (pintype "bidirectional"))
    )
    (net (code "78") (name "unconnected-(U1A-PC15-OSC32_OUT-Pad4)") (class "Default")
      (node (ref "U1") (pin "4") (pinfunction "PC15-OSC32_OUT_4") (pintype "bidirectional"))
    )
    (net (code "79") (name "unconnected-(U3A-NRST-Pad7)") (class "Default")
      (node (ref "U3") (pin "7") (pinfunction "NRST_7") (pintype "bidirectional"))
    )
    (net (code "80") (name "unconnected-(U3A-PA0-WKUP-Pad10)") (class "Default")
      (node (ref "U3") (pin "10") (pinfunction "PA0-WKUP_10") (pintype "bidirectional"))
    )
    (net (code "81") (name "unconnected-(U3A-PA1-Pad11)") (class "Default")
      (node (ref "U3") (pin "11") (pinfunction "PA1_11") (pintype "bidirectional"))
    )
    (net (code "82") (name "unconnected-(U3A-PA2-Pad12)") (class "Default")
      (node (ref "U3") (pin "12") (pinfunction "PA2_12") (pintype "bidirectional"))
    )
    (net (code "83") (name "unconnected-(U3A-PA3-Pad13)") (class "Default")
      (node (ref "U3") (pin "13") (pinfunction "PA3_13") (pintype "bidirectional"))
    )
    (net (code "84") (name "unconnected-(U3A-PA6-Pad16)") (class "Default")
      (node (ref "U3") (pin "16") (pinfunction "PA6_16") (pintype "bidirectional"))
    )
    (net (code "85") (name "unconnected-(U3A-PA7-Pad17)") (class "Default")
      (node (ref "U3") (pin "17") (pinfunction "PA7_17") (pintype "bidirectional"))
    )
    (net (code "86") (name "unconnected-(U3A-PA15-Pad38)") (class "Default")
      (node (ref "U3") (pin "38") (pinfunction "PA15_38") (pintype "bidirectional"))
    )
    (net (code "87") (name "unconnected-(U3A-PB3-Pad39)") (class "Default")
      (node (ref "U3") (pin "39") (pinfunction "PB3_39") (pintype "bidirectional"))
    )
    (net (code "88") (name "unconnected-(U3A-PB4-Pad40)") (class "Default")
      (node (ref "U3") (pin "40") (pinfunction "PB4_40") (pintype "bidirectional"))
    )
    (net (code "89") (name "unconnected-(U3A-PB7-Pad43)") (class "Default")
      (node (ref "U3") (pin "43") (pinfunction "PB7_43") (pintype "bidirectional"))
    )
    (net (code "90") (name "unconnected-(U3A-PB8-Pad45)") (class "Default")
      (node (ref "U3") (pin "45") (pinfunction "PB8_45") (pintype "bidirectional"))
    )
    (net (code "91") (name "unconnected-(U3A-PB9-Pad46)") (class "Default")
      (node (ref "U3") (pin "46") (pinfunction "PB9_46") (pintype "bidirectional"))
    )
    (net (code "92") (name "unconnected-(U3A-PB14-Pad27)") (class "Default")
      (node (ref "U3") (pin "27") (pinfunction "PB14_27") (pintype "bidirectional"))
    )
    (net (code "93") (name "unconnected-(U3A-PB15-Pad28)") (class "Default")
      (node (ref "U3") (pin "28") (pinfunction "PB15_28") (pintype "bidirectional"))
    )
    (net (code "94") (name "unconnected-(U3A-PC13-TAMPER-RTC-Pad2)") (class "Default")
      (node (ref "U3") (pin "2") (pinfunction "PC13-TAMPER-RTC_2") (pintype "bidirectional"))
    )
    (net (code "95") (name "unconnected-(U3A-PC14-OSC32_IN-Pad3)") (class "Default")
      (node (ref "U3") (pin "3") (pinfunction "PC14-OSC32_IN_3") (pintype "bidirectional"))
    )
    (net (code "96") (name "unconnected-(U3A-PC15-OSC32_OUT-Pad4)") (class "Default")
      (node (ref "U3") (pin "4") (pinfunction "PC15-OSC32_OUT_4") (pintype "bidirectional"))
    )
  )
)
